# BatteryController.net
KiCad netlist of a schematic drawn in Altium Designer
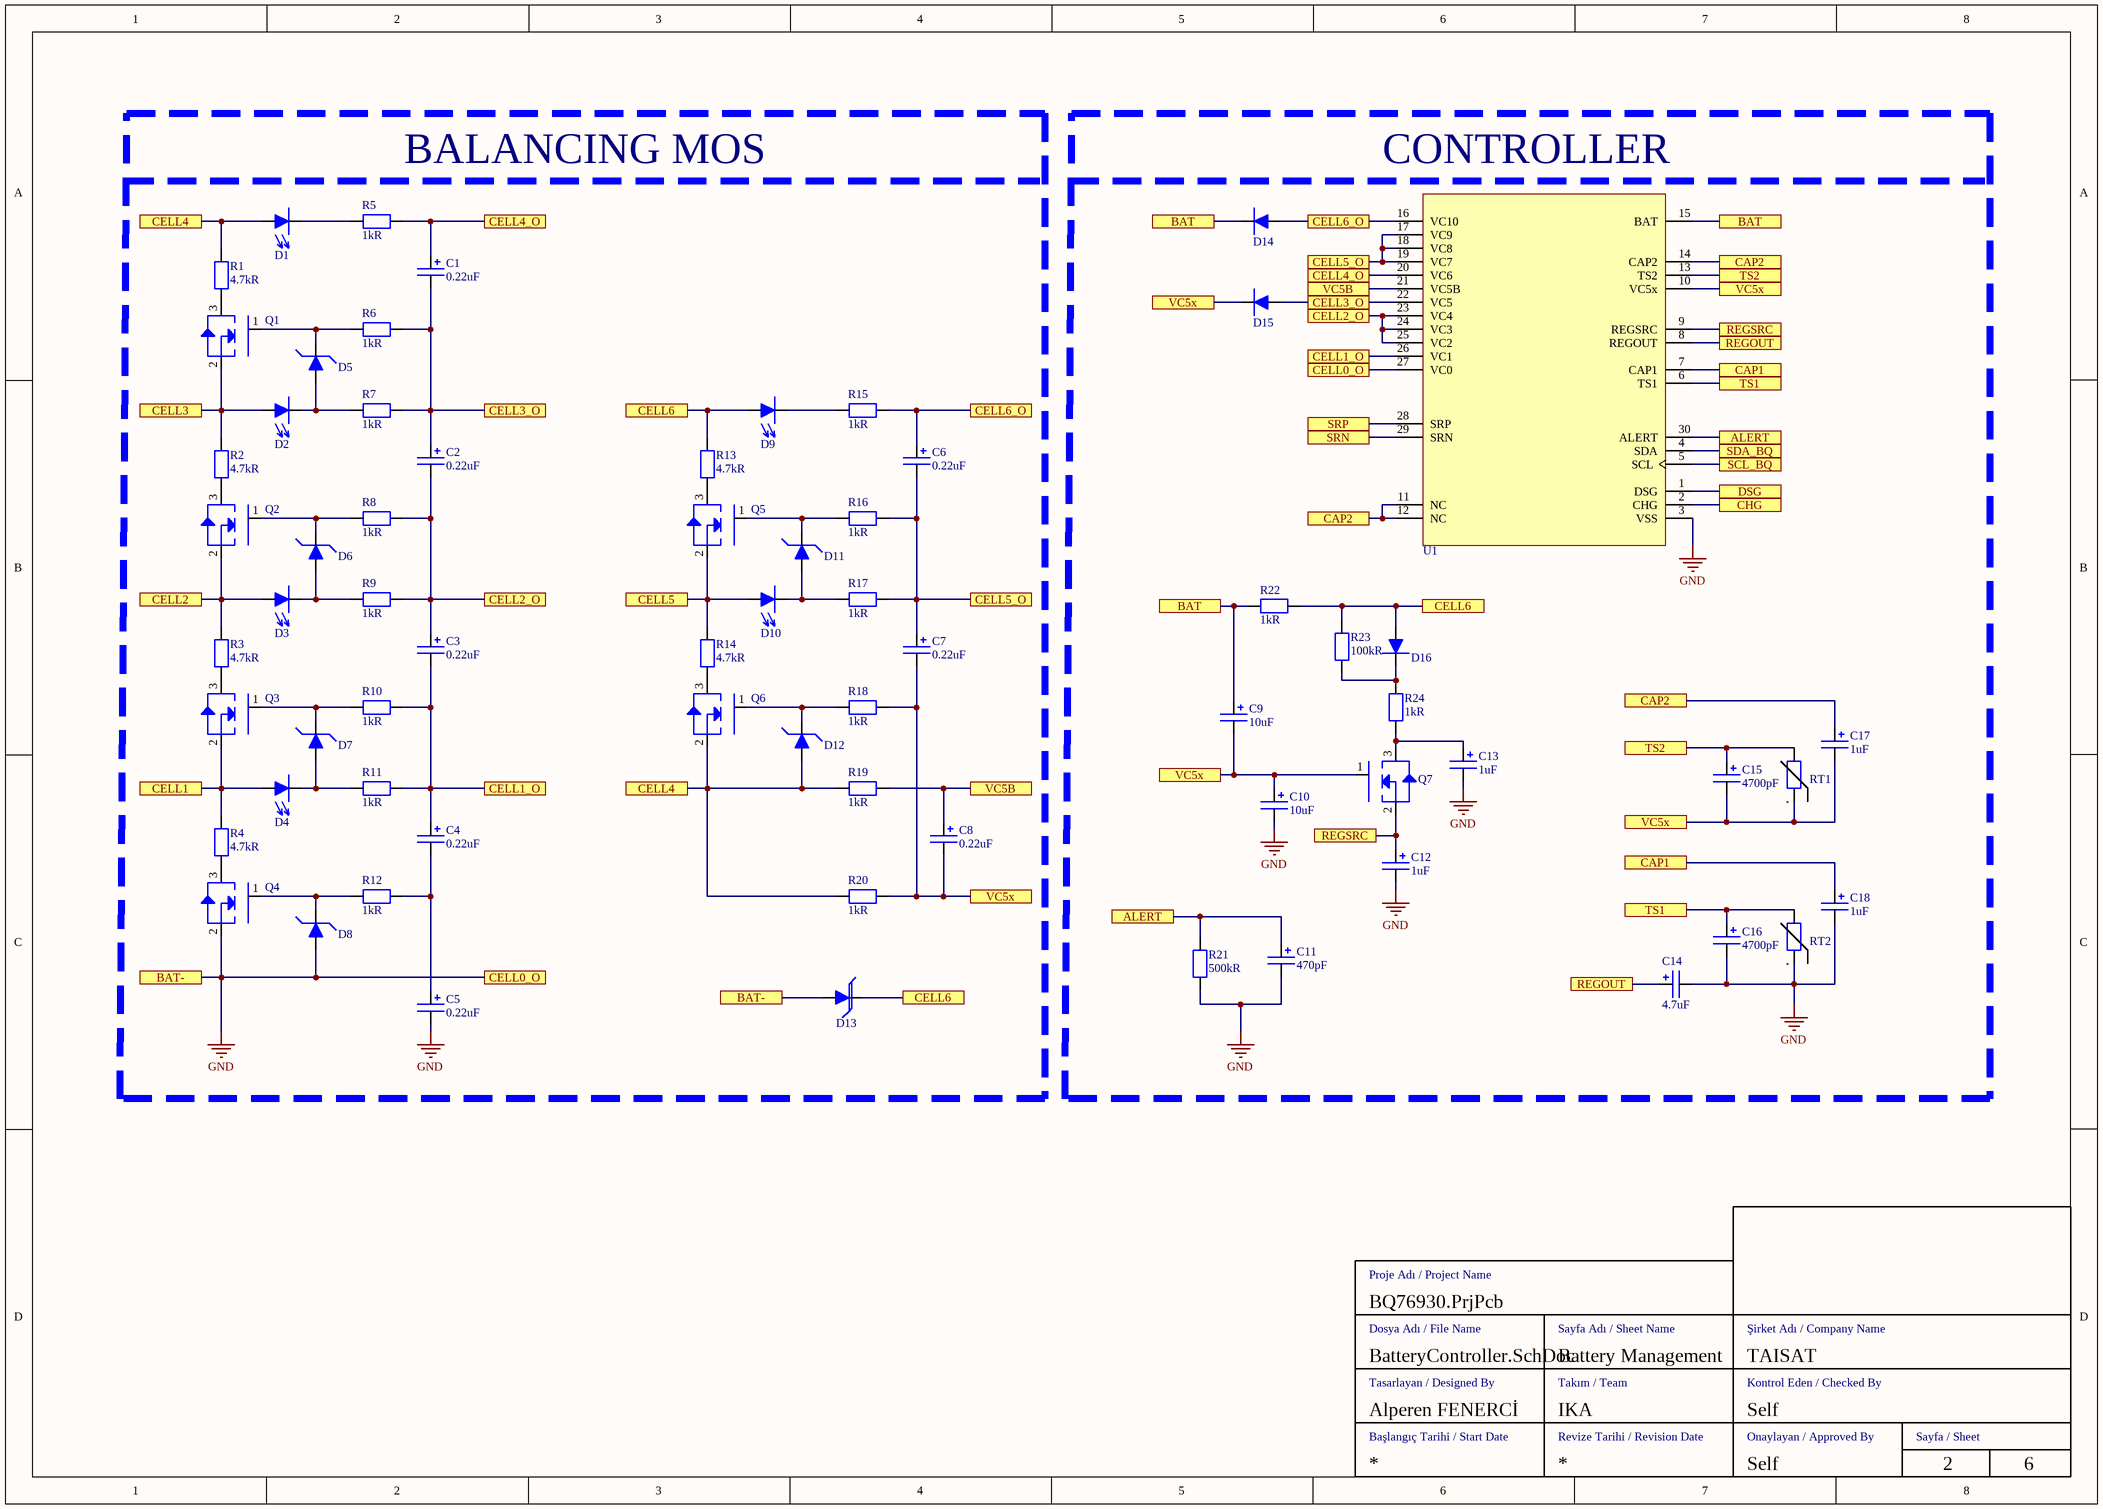
[diagram p0: BatteryController.SchDoc]

(export (version "E")
  (design (tool "Eeschema 10.0.6"))
  (components
    (comp (ref "C1")
      (value "0.22uF")
      (footprint "CAP 0603")
      (description "Multilayer Ceramic Capacitor")
      (fields (field (name "Comment") "CAP 0603"))
      (libsource (lib "Kaptanyums Lib") (part "CAP 0603"))
    )
    (comp (ref "C2")
      (value "0.22uF")
      (footprint "CAP 0603")
      (description "Multilayer Ceramic Capacitor")
      (fields (field (name "Comment") "CAP 0603"))
      (libsource (lib "Kaptanyums Lib") (part "CAP 0603"))
    )
    (comp (ref "C3")
      (value "0.22uF")
      (footprint "CAP 0603")
      (description "Multilayer Ceramic Capacitor")
      (fields (field (name "Comment") "CAP 0603"))
      (libsource (lib "Kaptanyums Lib") (part "CAP 0603"))
    )
    (comp (ref "C4")
      (value "0.22uF")
      (footprint "CAP 0603")
      (description "Multilayer Ceramic Capacitor")
      (fields (field (name "Comment") "CAP 0603"))
      (libsource (lib "Kaptanyums Lib") (part "CAP 0603"))
    )
    (comp (ref "C5")
      (value "0.22uF")
      (footprint "CAP 0603")
      (description "Multilayer Ceramic Capacitor")
      (fields (field (name "Comment") "CAP 0603"))
      (libsource (lib "Kaptanyums Lib") (part "CAP 0603"))
    )
    (comp (ref "C6")
      (value "0.22uF")
      (footprint "CAP 0603")
      (description "Multilayer Ceramic Capacitor")
      (fields (field (name "Comment") "CAP 0603"))
      (libsource (lib "Kaptanyums Lib") (part "CAP 0603"))
    )
    (comp (ref "C7")
      (value "0.22uF")
      (footprint "CAP 0603")
      (description "Multilayer Ceramic Capacitor")
      (fields (field (name "Comment") "CAP 0603"))
      (libsource (lib "Kaptanyums Lib") (part "CAP 0603"))
    )
    (comp (ref "C8")
      (value "0.22uF")
      (footprint "CAP 0603")
      (description "Multilayer Ceramic Capacitor")
      (fields (field (name "Comment") "CAP 0603"))
      (libsource (lib "Kaptanyums Lib") (part "CAP 0603"))
    )
    (comp (ref "C9")
      (value "10uF")
      (footprint "CAP 0603")
      (description "Multilayer Ceramic Capacitor")
      (fields (field (name "Comment") "CAP 0603"))
      (libsource (lib "Kaptanyums Lib") (part "CAP 0603"))
    )
    (comp (ref "C10")
      (value "10uF")
      (footprint "CAP 0603")
      (description "Multilayer Ceramic Capacitor")
      (fields (field (name "Comment") "CAP 0603"))
      (libsource (lib "Kaptanyums Lib") (part "CAP 0603"))
    )
    (comp (ref "C11")
      (value "470pF")
      (footprint "CAP 0603")
      (description "Multilayer Ceramic Capacitor")
      (fields (field (name "Comment") "CAP 0603"))
      (libsource (lib "Kaptanyums Lib") (part "CAP 0603"))
    )
    (comp (ref "C12")
      (value "1uF")
      (footprint "CAP 0603")
      (description "Multilayer Ceramic Capacitor")
      (fields (field (name "Comment") "CAP 0603"))
      (libsource (lib "Kaptanyums Lib") (part "CAP 0603"))
    )
    (comp (ref "C13")
      (value "1uF")
      (footprint "CAP 0603")
      (description "Multilayer Ceramic Capacitor")
      (fields (field (name "Comment") "CAP 0603"))
      (libsource (lib "Kaptanyums Lib") (part "CAP 0603"))
    )
    (comp (ref "C14")
      (value "4.7uF")
      (footprint "CAP 0603")
      (description "Multilayer Ceramic Capacitor")
      (fields (field (name "Comment") "CAP 0603"))
      (libsource (lib "Kaptanyums Lib") (part "CAP 0603"))
    )
    (comp (ref "C15")
      (value "4700pF")
      (footprint "CAP 0603")
      (description "Multilayer Ceramic Capacitor")
      (fields (field (name "Comment") "CAP 0603"))
      (libsource (lib "Kaptanyums Lib") (part "CAP 0603"))
    )
    (comp (ref "C16")
      (value "4700pF")
      (footprint "CAP 0603")
      (description "Multilayer Ceramic Capacitor")
      (fields (field (name "Comment") "CAP 0603"))
      (libsource (lib "Kaptanyums Lib") (part "CAP 0603"))
    )
    (comp (ref "C17")
      (value "1uF")
      (footprint "CAP 0603")
      (description "Multilayer Ceramic Capacitor")
      (fields (field (name "Comment") "CAP 0603"))
      (libsource (lib "Kaptanyums Lib") (part "CAP 0603"))
    )
    (comp (ref "C18")
      (value "1uF")
      (footprint "CAP 0603")
      (description "Multilayer Ceramic Capacitor")
      (fields (field (name "Comment") "CAP 0603"))
      (libsource (lib "Kaptanyums Lib") (part "CAP 0603"))
    )
    (comp (ref "D1")
      (value "LTW-C191TLA")
      (footprint "LED 0603")
      (description "Chip LED")
      (libsource (lib "Kaptanyums Lib") (part "LED 0603"))
    )
    (comp (ref "D2")
      (value "LTW-C191TLA")
      (footprint "LED 0603")
      (description "Chip LED")
      (libsource (lib "Kaptanyums Lib") (part "LED 0603"))
    )
    (comp (ref "D3")
      (value "LTW-C191TLA")
      (footprint "LED 0603")
      (description "Chip LED")
      (libsource (lib "Kaptanyums Lib") (part "LED 0603"))
    )
    (comp (ref "D4")
      (value "LTW-C191TLA")
      (footprint "LED 0603")
      (description "Chip LED")
      (libsource (lib "Kaptanyums Lib") (part "LED 0603"))
    )
    (comp (ref "D5")
      (value "MM3Z5V1T1G")
      (footprint "SOD323")
      (description "Diode Zener")
      (fields (field (name "VOLTAGE") "5.1V"))
      (libsource (lib "Kaptanyums Lib") (part "MM3Z5V1T1G"))
    )
    (comp (ref "D6")
      (value "MM3Z5V1T1G")
      (footprint "SOD323")
      (description "Diode Zener")
      (fields (field (name "VOLTAGE") "5.1V"))
      (libsource (lib "Kaptanyums Lib") (part "MM3Z5V1T1G"))
    )
    (comp (ref "D7")
      (value "MM3Z5V1T1G")
      (footprint "SOD323")
      (description "Diode Zener")
      (fields (field (name "VOLTAGE") "5.1V"))
      (libsource (lib "Kaptanyums Lib") (part "MM3Z5V1T1G"))
    )
    (comp (ref "D8")
      (value "MM3Z5V1T1G")
      (footprint "SOD323")
      (description "Diode Zener")
      (fields (field (name "VOLTAGE") "5.1V"))
      (libsource (lib "Kaptanyums Lib") (part "MM3Z5V1T1G"))
    )
    (comp (ref "D9")
      (value "LTW-C191TLA")
      (footprint "LED 0603")
      (description "Chip LED")
      (libsource (lib "Kaptanyums Lib") (part "LED 0603"))
    )
    (comp (ref "D10")
      (value "LTW-C191TLA")
      (footprint "LED 0603")
      (description "Chip LED")
      (libsource (lib "Kaptanyums Lib") (part "LED 0603"))
    )
    (comp (ref "D11")
      (value "MM3Z5V1T1G")
      (footprint "SOD323")
      (description "Diode Zener")
      (fields (field (name "VOLTAGE") "5.1V"))
      (libsource (lib "Kaptanyums Lib") (part "MM3Z5V1T1G"))
    )
    (comp (ref "D12")
      (value "MM3Z5V1T1G")
      (footprint "SOD323")
      (description "Diode Zener")
      (fields (field (name "VOLTAGE") "5.1V"))
      (libsource (lib "Kaptanyums Lib") (part "MM3Z5V1T1G"))
    )
    (comp (ref "D13")
      (value "SMAJ36A-HT")
      (footprint "DO214AC")
      (description "Diode TVS")
      (fields (field (name "VOLTAGE") "36V"))
      (libsource (lib "Kaptanyums Lib") (part "SMAJ36A-HT"))
    )
    (comp (ref "D14")
      (value "BAV20W-7-F")
      (footprint "SOD123")
      (description "Diode Switch")
      (fields (field (name "VOLTAGE") "150V"))
      (libsource (lib "Kaptanyums Lib") (part "BAV20W-7-F"))
    )
    (comp (ref "D15")
      (value "BAV20W-7-F")
      (footprint "SOD123")
      (description "Diode Switch")
      (fields (field (name "VOLTAGE") "150V"))
      (libsource (lib "Kaptanyums Lib") (part "BAV20W-7-F"))
    )
    (comp (ref "D16")
      (value "1N4148WS")
      (footprint "SOD323")
      (description "Diode Gen")
      (fields (field (name "VOLTAGE") "75V"))
      (libsource (lib "Kaptanyums Lib") (part "1N4148WS"))
    )
    (comp (ref "Q1")
      (value "2N7002K")
      (footprint "SOT23-3")
      (description "MOSFET")
      (fields (field (name "VOLTAGE") "60V"))
      (libsource (lib "Kaptanyums Lib") (part "2N7002K"))
    )
    (comp (ref "Q2")
      (value "2N7002K")
      (footprint "SOT23-3")
      (description "MOSFET")
      (fields (field (name "VOLTAGE") "60V"))
      (libsource (lib "Kaptanyums Lib") (part "2N7002K"))
    )
    (comp (ref "Q3")
      (value "2N7002K")
      (footprint "SOT23-3")
      (description "MOSFET")
      (fields (field (name "VOLTAGE") "60V"))
      (libsource (lib "Kaptanyums Lib") (part "2N7002K"))
    )
    (comp (ref "Q4")
      (value "2N7002K")
      (footprint "SOT23-3")
      (description "MOSFET")
      (fields (field (name "VOLTAGE") "60V"))
      (libsource (lib "Kaptanyums Lib") (part "2N7002K"))
    )
    (comp (ref "Q5")
      (value "2N7002K")
      (footprint "SOT23-3")
      (description "MOSFET")
      (fields (field (name "VOLTAGE") "60V"))
      (libsource (lib "Kaptanyums Lib") (part "2N7002K"))
    )
    (comp (ref "Q6")
      (value "2N7002K")
      (footprint "SOT23-3")
      (description "MOSFET")
      (fields (field (name "VOLTAGE") "60V"))
      (libsource (lib "Kaptanyums Lib") (part "2N7002K"))
    )
    (comp (ref "Q7")
      (value "2N7002K")
      (footprint "SOT23-3")
      (description "MOSFET")
      (fields (field (name "VOLTAGE") "60V"))
      (libsource (lib "Kaptanyums Lib") (part "2N7002K"))
    )
    (comp (ref "R1")
      (value "4.7kR")
      (footprint "RESISTOR 1206")
      (description "SMD Chip Resistor")
      (fields (field (name "Comment") "RES 1206"))
      (libsource (lib "Kaptanyums Lib") (part "RES 1206"))
    )
    (comp (ref "R2")
      (value "4.7kR")
      (footprint "RESISTOR 1206")
      (description "SMD Chip Resistor")
      (fields (field (name "Comment") "RES 1206"))
      (libsource (lib "Kaptanyums Lib") (part "RES 1206"))
    )
    (comp (ref "R3")
      (value "4.7kR")
      (footprint "RESISTOR 1206")
      (description "SMD Chip Resistor")
      (fields (field (name "Comment") "RES 1206"))
      (libsource (lib "Kaptanyums Lib") (part "RES 1206"))
    )
    (comp (ref "R4")
      (value "4.7kR")
      (footprint "RESISTOR 1206")
      (description "SMD Chip Resistor")
      (fields (field (name "Comment") "RES 1206"))
      (libsource (lib "Kaptanyums Lib") (part "RES 1206"))
    )
    (comp (ref "R5")
      (value "1kR")
      (footprint "RESISTOR 0603")
      (description "SMD Chip Resistor")
      (fields (field (name "Comment") "RES 0603"))
      (libsource (lib "Kaptanyums Lib") (part "RES 0603"))
    )
    (comp (ref "R6")
      (value "1kR")
      (footprint "RESISTOR 0603")
      (description "SMD Chip Resistor")
      (fields (field (name "Comment") "RES 0603"))
      (libsource (lib "Kaptanyums Lib") (part "RES 0603"))
    )
    (comp (ref "R7")
      (value "1kR")
      (footprint "RESISTOR 0603")
      (description "SMD Chip Resistor")
      (fields (field (name "Comment") "RES 0603"))
      (libsource (lib "Kaptanyums Lib") (part "RES 0603"))
    )
    (comp (ref "R8")
      (value "1kR")
      (footprint "RESISTOR 0603")
      (description "SMD Chip Resistor")
      (fields (field (name "Comment") "RES 0603"))
      (libsource (lib "Kaptanyums Lib") (part "RES 0603"))
    )
    (comp (ref "R9")
      (value "1kR")
      (footprint "RESISTOR 0603")
      (description "SMD Chip Resistor")
      (fields (field (name "Comment") "RES 0603"))
      (libsource (lib "Kaptanyums Lib") (part "RES 0603"))
    )
    (comp (ref "R10")
      (value "1kR")
      (footprint "RESISTOR 0603")
      (description "SMD Chip Resistor")
      (fields (field (name "Comment") "RES 0603"))
      (libsource (lib "Kaptanyums Lib") (part "RES 0603"))
    )
    (comp (ref "R11")
      (value "1kR")
      (footprint "RESISTOR 0603")
      (description "SMD Chip Resistor")
      (fields (field (name "Comment") "RES 0603"))
      (libsource (lib "Kaptanyums Lib") (part "RES 0603"))
    )
    (comp (ref "R12")
      (value "1kR")
      (footprint "RESISTOR 0603")
      (description "SMD Chip Resistor")
      (fields (field (name "Comment") "RES 0603"))
      (libsource (lib "Kaptanyums Lib") (part "RES 0603"))
    )
    (comp (ref "R13")
      (value "4.7kR")
      (footprint "RESISTOR 1206")
      (description "SMD Chip Resistor")
      (fields (field (name "Comment") "RES 1206"))
      (libsource (lib "Kaptanyums Lib") (part "RES 1206"))
    )
    (comp (ref "R14")
      (value "4.7kR")
      (footprint "RESISTOR 1206")
      (description "SMD Chip Resistor")
      (fields (field (name "Comment") "RES 1206"))
      (libsource (lib "Kaptanyums Lib") (part "RES 1206"))
    )
    (comp (ref "R15")
      (value "1kR")
      (footprint "RESISTOR 0603")
      (description "SMD Chip Resistor")
      (fields (field (name "Comment") "RES 0603"))
      (libsource (lib "Kaptanyums Lib") (part "RES 0603"))
    )
    (comp (ref "R16")
      (value "1kR")
      (footprint "RESISTOR 0603")
      (description "SMD Chip Resistor")
      (fields (field (name "Comment") "RES 0603"))
      (libsource (lib "Kaptanyums Lib") (part "RES 0603"))
    )
    (comp (ref "R17")
      (value "1kR")
      (footprint "RESISTOR 0603")
      (description "SMD Chip Resistor")
      (fields (field (name "Comment") "RES 0603"))
      (libsource (lib "Kaptanyums Lib") (part "RES 0603"))
    )
    (comp (ref "R18")
      (value "1kR")
      (footprint "RESISTOR 0603")
      (description "SMD Chip Resistor")
      (fields (field (name "Comment") "RES 0603"))
      (libsource (lib "Kaptanyums Lib") (part "RES 0603"))
    )
    (comp (ref "R19")
      (value "1kR")
      (footprint "RESISTOR 0603")
      (description "SMD Chip Resistor")
      (fields (field (name "Comment") "RES 0603"))
      (libsource (lib "Kaptanyums Lib") (part "RES 0603"))
    )
    (comp (ref "R20")
      (value "1kR")
      (footprint "RESISTOR 0603")
      (description "SMD Chip Resistor")
      (fields (field (name "Comment") "RES 0603"))
      (libsource (lib "Kaptanyums Lib") (part "RES 0603"))
    )
    (comp (ref "R21")
      (value "500kR")
      (footprint "RESISTOR 0603")
      (description "SMD Chip Resistor")
      (fields (field (name "Comment") "RES 0603"))
      (libsource (lib "Kaptanyums Lib") (part "RES 0603"))
    )
    (comp (ref "R22")
      (value "1kR")
      (footprint "RESISTOR 0603")
      (description "SMD Chip Resistor")
      (fields (field (name "Comment") "RES 0603"))
      (libsource (lib "Kaptanyums Lib") (part "RES 0603"))
    )
    (comp (ref "R23")
      (value "100kR")
      (footprint "RESISTOR 0603")
      (description "SMD Chip Resistor")
      (fields (field (name "Comment") "RES 0603"))
      (libsource (lib "Kaptanyums Lib") (part "RES 0603"))
    )
    (comp (ref "R24")
      (value "1kR")
      (footprint "RESISTOR 0603")
      (description "SMD Chip Resistor")
      (fields (field (name "Comment") "RES 0603"))
      (libsource (lib "Kaptanyums Lib") (part "RES 0603"))
    )
    (comp (ref "RT1")
      (value "NTC 0603")
      (footprint "NTC 0603")
      (description "Thermistor NTC")
      (libsource (lib "Kaptanyums Lib") (part "NTC 0603"))
    )
    (comp (ref "RT2")
      (value "NTC 0603")
      (footprint "NTC 0603")
      (description "Thermistor NTC")
      (libsource (lib "Kaptanyums Lib") (part "NTC 0603"))
    )
    (comp (ref "U1")
      (value "BQ76930")
      (footprint "TSSOP-30")
      (description "Cell Balance, Cell Monitoring")
      (libsource (lib "Kaptanyums Lib") (part "BQ76930"))
    )
  )
  (nets
    (net (code "1") (name "/ALERT") (class "Default")
      (node (ref "C11") (pin "1") (pinfunction "1_1") (pintype "passive"))
      (node (ref "R21") (pin "2") (pinfunction "2_2") (pintype "passive"))
      (node (ref "U1") (pin "30") (pinfunction "ALERT_30") (pintype "passive"))
    )
    (net (code "2") (name "/BAT") (class "Default")
      (node (ref "C9") (pin "1") (pinfunction "1_1") (pintype "passive"))
      (node (ref "D14") (pin "1") (pinfunction "1_1") (pintype "passive"))
      (node (ref "R22") (pin "2") (pinfunction "2_2") (pintype "passive"))
      (node (ref "U1") (pin "15") (pinfunction "BAT_15") (pintype "passive"))
    )
    (net (code "3") (name "/CAP1") (class "Default")
      (node (ref "C18") (pin "1") (pinfunction "1_1") (pintype "passive"))
      (node (ref "U1") (pin "7") (pinfunction "CAP1_7") (pintype "passive"))
    )
    (net (code "4") (name "/CAP2") (class "Default")
      (node (ref "C17") (pin "1") (pinfunction "1_1") (pintype "passive"))
      (node (ref "U1") (pin "11") (pinfunction "NC_11") (pintype "passive"))
      (node (ref "U1") (pin "12") (pinfunction "NC_12") (pintype "passive"))
      (node (ref "U1") (pin "14") (pinfunction "CAP2_14") (pintype "passive"))
    )
    (net (code "5") (name "/CELL1") (class "Default")
      (node (ref "D4") (pin "2") (pinfunction "2_2") (pintype "passive"))
      (node (ref "Q3") (pin "2") (pinfunction "S_2") (pintype "passive"))
      (node (ref "R4") (pin "2") (pinfunction "2_2") (pintype "passive"))
    )
    (net (code "6") (name "/CELL1_O") (class "Default")
      (node (ref "C3") (pin "2") (pinfunction "2_2") (pintype "passive"))
      (node (ref "C4") (pin "1") (pinfunction "1_1") (pintype "passive"))
      (node (ref "R10") (pin "1") (pinfunction "1_1") (pintype "passive"))
      (node (ref "R11") (pin "1") (pinfunction "1_1") (pintype "passive"))
      (node (ref "U1") (pin "26") (pinfunction "VC1_26") (pintype "passive"))
    )
    (net (code "7") (name "/CELL2") (class "Default")
      (node (ref "D3") (pin "2") (pinfunction "2_2") (pintype "passive"))
      (node (ref "Q2") (pin "2") (pinfunction "S_2") (pintype "passive"))
      (node (ref "R3") (pin "2") (pinfunction "2_2") (pintype "passive"))
    )
    (net (code "8") (name "/CELL2_O") (class "Default")
      (node (ref "C2") (pin "2") (pinfunction "2_2") (pintype "passive"))
      (node (ref "C3") (pin "1") (pinfunction "1_1") (pintype "passive"))
      (node (ref "R8") (pin "1") (pinfunction "1_1") (pintype "passive"))
      (node (ref "R9") (pin "1") (pinfunction "1_1") (pintype "passive"))
      (node (ref "U1") (pin "23") (pinfunction "VC4_23") (pintype "passive"))
      (node (ref "U1") (pin "24") (pinfunction "VC3_24") (pintype "passive"))
      (node (ref "U1") (pin "25") (pinfunction "VC2_25") (pintype "passive"))
    )
    (net (code "9") (name "/CELL3") (class "Default")
      (node (ref "D2") (pin "2") (pinfunction "2_2") (pintype "passive"))
      (node (ref "Q1") (pin "2") (pinfunction "S_2") (pintype "passive"))
      (node (ref "R2") (pin "2") (pinfunction "2_2") (pintype "passive"))
    )
    (net (code "10") (name "/CELL3_O") (class "Default")
      (node (ref "C1") (pin "2") (pinfunction "2_2") (pintype "passive"))
      (node (ref "C2") (pin "1") (pinfunction "1_1") (pintype "passive"))
      (node (ref "D15") (pin "2") (pinfunction "2_2") (pintype "passive"))
      (node (ref "R6") (pin "1") (pinfunction "1_1") (pintype "passive"))
      (node (ref "R7") (pin "1") (pinfunction "1_1") (pintype "passive"))
      (node (ref "U1") (pin "22") (pinfunction "VC5_22") (pintype "passive"))
    )
    (net (code "11") (name "/CELL4") (class "Default")
      (node (ref "D1") (pin "2") (pinfunction "2_2") (pintype "passive"))
      (node (ref "D12") (pin "2") (pinfunction "2_2") (pintype "passive"))
      (node (ref "Q6") (pin "2") (pinfunction "S_2") (pintype "passive"))
      (node (ref "R1") (pin "2") (pinfunction "2_2") (pintype "passive"))
      (node (ref "R19") (pin "2") (pinfunction "2_2") (pintype "passive"))
      (node (ref "R20") (pin "2") (pinfunction "2_2") (pintype "passive"))
    )
    (net (code "12") (name "/CELL4_O") (class "Default")
      (node (ref "C1") (pin "1") (pinfunction "1_1") (pintype "passive"))
      (node (ref "R5") (pin "1") (pinfunction "1_1") (pintype "passive"))
      (node (ref "U1") (pin "20") (pinfunction "VC6_20") (pintype "passive"))
    )
    (net (code "13") (name "/CELL5") (class "Default")
      (node (ref "D10") (pin "2") (pinfunction "2_2") (pintype "passive"))
      (node (ref "Q5") (pin "2") (pinfunction "S_2") (pintype "passive"))
      (node (ref "R14") (pin "2") (pinfunction "2_2") (pintype "passive"))
    )
    (net (code "14") (name "/CELL5_O") (class "Default")
      (node (ref "C6") (pin "2") (pinfunction "2_2") (pintype "passive"))
      (node (ref "C7") (pin "1") (pinfunction "1_1") (pintype "passive"))
      (node (ref "R16") (pin "1") (pinfunction "1_1") (pintype "passive"))
      (node (ref "R17") (pin "1") (pinfunction "1_1") (pintype "passive"))
      (node (ref "U1") (pin "17") (pinfunction "VC9_17") (pintype "passive"))
      (node (ref "U1") (pin "18") (pinfunction "VC8_18") (pintype "passive"))
      (node (ref "U1") (pin "19") (pinfunction "VC7_19") (pintype "passive"))
    )
    (net (code "15") (name "/CELL6") (class "Default")
      (node (ref "D13") (pin "1") (pinfunction "1_1") (pintype "passive"))
      (node (ref "D16") (pin "2") (pinfunction "2_2") (pintype "passive"))
      (node (ref "D9") (pin "2") (pinfunction "2_2") (pintype "passive"))
      (node (ref "R13") (pin "2") (pinfunction "2_2") (pintype "passive"))
      (node (ref "R22") (pin "1") (pinfunction "1_1") (pintype "passive"))
      (node (ref "R23") (pin "2") (pinfunction "2_2") (pintype "passive"))
    )
    (net (code "16") (name "/CELL6_O") (class "Default")
      (node (ref "C6") (pin "1") (pinfunction "1_1") (pintype "passive"))
      (node (ref "D14") (pin "2") (pinfunction "2_2") (pintype "passive"))
      (node (ref "R15") (pin "1") (pinfunction "1_1") (pintype "passive"))
      (node (ref "U1") (pin "16") (pinfunction "VC10_16") (pintype "passive"))
    )
    (net (code "17") (name "/CHG") (class "Default")
      (node (ref "U1") (pin "2") (pinfunction "CHG_2") (pintype "passive"))
    )
    (net (code "18") (name "/DSG") (class "Default")
      (node (ref "U1") (pin "1") (pinfunction "DSG_1") (pintype "passive"))
    )
    (net (code "19") (name "/REGOUT") (class "Default")
      (node (ref "C14") (pin "1") (pinfunction "1_1") (pintype "passive"))
      (node (ref "U1") (pin "8") (pinfunction "REGOUT_8") (pintype "passive"))
    )
    (net (code "20") (name "/REGSRC") (class "Default")
      (node (ref "C12") (pin "1") (pinfunction "1_1") (pintype "passive"))
      (node (ref "Q7") (pin "2") (pinfunction "S_2") (pintype "passive"))
      (node (ref "U1") (pin "9") (pinfunction "REGSRC_9") (pintype "passive"))
    )
    (net (code "21") (name "/SCL_BQ") (class "Default")
      (node (ref "U1") (pin "5") (pinfunction "SCL_5") (pintype "passive"))
    )
    (net (code "22") (name "/SDA_BQ") (class "Default")
      (node (ref "U1") (pin "4") (pinfunction "SDA_4") (pintype "passive"))
    )
    (net (code "23") (name "/SRN") (class "Default")
      (node (ref "U1") (pin "29") (pinfunction "SRN_29") (pintype "passive"))
    )
    (net (code "24") (name "/SRP") (class "Default")
      (node (ref "U1") (pin "28") (pinfunction "SRP_28") (pintype "passive"))
    )
    (net (code "25") (name "/TS1") (class "Default")
      (node (ref "C16") (pin "1") (pinfunction "1_1") (pintype "passive"))
      (node (ref "RT2") (pin "2") (pinfunction "2_2") (pintype "passive"))
      (node (ref "U1") (pin "6") (pinfunction "TS1_6") (pintype "passive"))
    )
    (net (code "26") (name "/TS2") (class "Default")
      (node (ref "C15") (pin "1") (pinfunction "1_1") (pintype "passive"))
      (node (ref "RT1") (pin "2") (pinfunction "2_2") (pintype "passive"))
      (node (ref "U1") (pin "13") (pinfunction "TS2_13") (pintype "passive"))
    )
    (net (code "27") (name "/VC5B") (class "Default")
      (node (ref "C8") (pin "1") (pinfunction "1_1") (pintype "passive"))
      (node (ref "R19") (pin "1") (pinfunction "1_1") (pintype "passive"))
      (node (ref "U1") (pin "21") (pinfunction "VC5B_21") (pintype "passive"))
    )
    (net (code "28") (name "/VC5x") (class "Default")
      (node (ref "C10") (pin "1") (pinfunction "1_1") (pintype "passive"))
      (node (ref "C15") (pin "2") (pinfunction "2_2") (pintype "passive"))
      (node (ref "C17") (pin "2") (pinfunction "2_2") (pintype "passive"))
      (node (ref "C7") (pin "2") (pinfunction "2_2") (pintype "passive"))
      (node (ref "C8") (pin "2") (pinfunction "2_2") (pintype "passive"))
      (node (ref "C9") (pin "2") (pinfunction "2_2") (pintype "passive"))
      (node (ref "D15") (pin "1") (pinfunction "1_1") (pintype "passive"))
      (node (ref "Q7") (pin "1") (pinfunction "G_1") (pintype "passive"))
      (node (ref "R18") (pin "1") (pinfunction "1_1") (pintype "passive"))
      (node (ref "R20") (pin "1") (pinfunction "1_1") (pintype "passive"))
      (node (ref "RT1") (pin "1") (pinfunction "1_1") (pintype "passive"))
      (node (ref "U1") (pin "10") (pinfunction "VC5x_10") (pintype "passive"))
    )
    (net (code "29") (name "GND") (class "Default")
      (node (ref "C10") (pin "2") (pinfunction "2_2") (pintype "passive"))
      (node (ref "C11") (pin "2") (pinfunction "2_2") (pintype "passive"))
      (node (ref "C12") (pin "2") (pinfunction "2_2") (pintype "passive"))
      (node (ref "C13") (pin "2") (pinfunction "2_2") (pintype "passive"))
      (node (ref "C14") (pin "2") (pinfunction "2_2") (pintype "passive"))
      (node (ref "C16") (pin "2") (pinfunction "2_2") (pintype "passive"))
      (node (ref "C18") (pin "2") (pinfunction "2_2") (pintype "passive"))
      (node (ref "C5") (pin "2") (pinfunction "2_2") (pintype "passive"))
      (node (ref "D13") (pin "2") (pinfunction "2_2") (pintype "passive"))
      (node (ref "D8") (pin "2") (pinfunction "2_2") (pintype "passive"))
      (node (ref "Q4") (pin "2") (pinfunction "S_2") (pintype "passive"))
      (node (ref "R21") (pin "1") (pinfunction "1_1") (pintype "passive"))
      (node (ref "RT2") (pin "1") (pinfunction "1_1") (pintype "passive"))
      (node (ref "U1") (pin "27") (pinfunction "VC0_27") (pintype "passive"))
      (node (ref "U1") (pin "3") (pinfunction "VSS_3") (pintype "passive"))
    )
    (net (code "30") (name "Net-(C4-Pad2)") (class "Default")
      (node (ref "C4") (pin "2") (pinfunction "2_2") (pintype "passive"))
      (node (ref "C5") (pin "1") (pinfunction "1_1") (pintype "passive"))
      (node (ref "R12") (pin "1") (pinfunction "1_1") (pintype "passive"))
    )
    (net (code "31") (name "Net-(D1-Pad1)") (class "Default")
      (node (ref "D1") (pin "1") (pinfunction "1_1") (pintype "passive"))
      (node (ref "R5") (pin "2") (pinfunction "2_2") (pintype "passive"))
    )
    (net (code "32") (name "Net-(D2-Pad1)") (class "Default")
      (node (ref "D2") (pin "1") (pinfunction "1_1") (pintype "passive"))
      (node (ref "D5") (pin "2") (pinfunction "2_2") (pintype "passive"))
      (node (ref "R7") (pin "2") (pinfunction "2_2") (pintype "passive"))
    )
    (net (code "33") (name "Net-(D3-Pad1)") (class "Default")
      (node (ref "D3") (pin "1") (pinfunction "1_1") (pintype "passive"))
      (node (ref "D6") (pin "2") (pinfunction "2_2") (pintype "passive"))
      (node (ref "R9") (pin "2") (pinfunction "2_2") (pintype "passive"))
    )
    (net (code "34") (name "Net-(D4-Pad1)") (class "Default")
      (node (ref "D4") (pin "1") (pinfunction "1_1") (pintype "passive"))
      (node (ref "D7") (pin "2") (pinfunction "2_2") (pintype "passive"))
      (node (ref "R11") (pin "2") (pinfunction "2_2") (pintype "passive"))
    )
    (net (code "35") (name "Net-(D9-Pad1)") (class "Default")
      (node (ref "D9") (pin "1") (pinfunction "1_1") (pintype "passive"))
      (node (ref "R15") (pin "2") (pinfunction "2_2") (pintype "passive"))
    )
    (net (code "36") (name "Net-(D10-Pad1)") (class "Default")
      (node (ref "D10") (pin "1") (pinfunction "1_1") (pintype "passive"))
      (node (ref "D11") (pin "2") (pinfunction "2_2") (pintype "passive"))
      (node (ref "R17") (pin "2") (pinfunction "2_2") (pintype "passive"))
    )
    (net (code "37") (name "Net-(D16-Pad1)") (class "Default")
      (node (ref "D16") (pin "1") (pinfunction "1_1") (pintype "passive"))
      (node (ref "R23") (pin "1") (pinfunction "1_1") (pintype "passive"))
      (node (ref "R24") (pin "2") (pinfunction "2_2") (pintype "passive"))
    )
    (net (code "38") (name "Net-(Q1-D)") (class "Default")
      (node (ref "Q1") (pin "3") (pinfunction "D_3") (pintype "passive"))
      (node (ref "R1") (pin "1") (pinfunction "1_1") (pintype "passive"))
    )
    (net (code "39") (name "Net-(Q1-G)") (class "Default")
      (node (ref "D5") (pin "1") (pinfunction "1_1") (pintype "passive"))
      (node (ref "Q1") (pin "1") (pinfunction "G_1") (pintype "passive"))
      (node (ref "R6") (pin "2") (pinfunction "2_2") (pintype "passive"))
    )
    (net (code "40") (name "Net-(Q2-D)") (class "Default")
      (node (ref "Q2") (pin "3") (pinfunction "D_3") (pintype "passive"))
      (node (ref "R2") (pin "1") (pinfunction "1_1") (pintype "passive"))
    )
    (net (code "41") (name "Net-(Q2-G)") (class "Default")
      (node (ref "D6") (pin "1") (pinfunction "1_1") (pintype "passive"))
      (node (ref "Q2") (pin "1") (pinfunction "G_1") (pintype "passive"))
      (node (ref "R8") (pin "2") (pinfunction "2_2") (pintype "passive"))
    )
    (net (code "42") (name "Net-(Q3-D)") (class "Default")
      (node (ref "Q3") (pin "3") (pinfunction "D_3") (pintype "passive"))
      (node (ref "R3") (pin "1") (pinfunction "1_1") (pintype "passive"))
    )
    (net (code "43") (name "Net-(Q3-G)") (class "Default")
      (node (ref "D7") (pin "1") (pinfunction "1_1") (pintype "passive"))
      (node (ref "Q3") (pin "1") (pinfunction "G_1") (pintype "passive"))
      (node (ref "R10") (pin "2") (pinfunction "2_2") (pintype "passive"))
    )
    (net (code "44") (name "Net-(Q4-D)") (class "Default")
      (node (ref "Q4") (pin "3") (pinfunction "D_3") (pintype "passive"))
      (node (ref "R4") (pin "1") (pinfunction "1_1") (pintype "passive"))
    )
    (net (code "45") (name "Net-(Q4-G)") (class "Default")
      (node (ref "D8") (pin "1") (pinfunction "1_1") (pintype "passive"))
      (node (ref "Q4") (pin "1") (pinfunction "G_1") (pintype "passive"))
      (node (ref "R12") (pin "2") (pinfunction "2_2") (pintype "passive"))
    )
    (net (code "46") (name "Net-(Q5-D)") (class "Default")
      (node (ref "Q5") (pin "3") (pinfunction "D_3") (pintype "passive"))
      (node (ref "R13") (pin "1") (pinfunction "1_1") (pintype "passive"))
    )
    (net (code "47") (name "Net-(Q5-G)") (class "Default")
      (node (ref "D11") (pin "1") (pinfunction "1_1") (pintype "passive"))
      (node (ref "Q5") (pin "1") (pinfunction "G_1") (pintype "passive"))
      (node (ref "R16") (pin "2") (pinfunction "2_2") (pintype "passive"))
    )
    (net (code "48") (name "Net-(Q6-D)") (class "Default")
      (node (ref "Q6") (pin "3") (pinfunction "D_3") (pintype "passive"))
      (node (ref "R14") (pin "1") (pinfunction "1_1") (pintype "passive"))
    )
    (net (code "49") (name "Net-(Q6-G)") (class "Default")
      (node (ref "D12") (pin "1") (pinfunction "1_1") (pintype "passive"))
      (node (ref "Q6") (pin "1") (pinfunction "G_1") (pintype "passive"))
      (node (ref "R18") (pin "2") (pinfunction "2_2") (pintype "passive"))
    )
    (net (code "50") (name "Net-(Q7-D)") (class "Default")
      (node (ref "C13") (pin "1") (pinfunction "1_1") (pintype "passive"))
      (node (ref "Q7") (pin "3") (pinfunction "D_3") (pintype "passive"))
      (node (ref "R24") (pin "1") (pinfunction "1_1") (pintype "passive"))
    )
  )
)
